# BootSel-Atmega.net
KiCad netlist of a schematic drawn in EAGLE
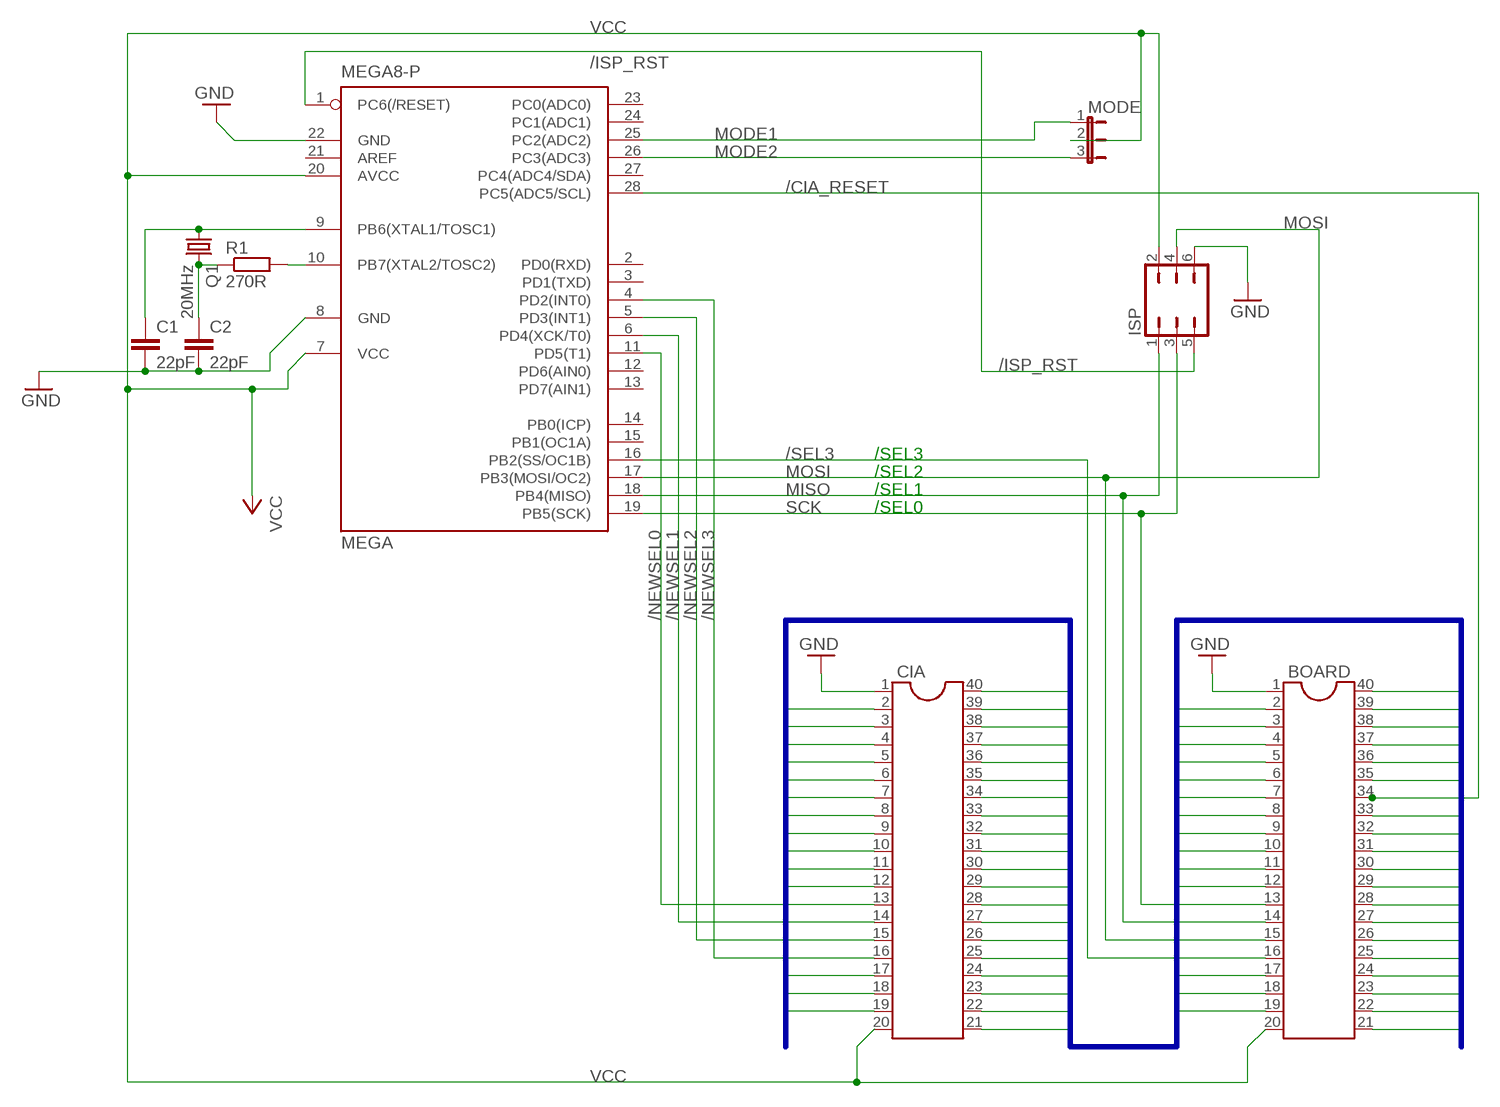
[diagram p0: schematic, sheet 1]

(export (version "E")
  (design (tool "Eeschema 10.0.6"))
  (components
    (comp (ref "BOARD")
      (value "DIL40")
      (footprint "eagle-import:DIL40")
      (libsource (lib "eagle-import") (part "DIL40"))
    )
    (comp (ref "C1")
      (value "22pF")
      (footprint "eagle-import:C2.5-4")
      (libsource (lib "eagle-import") (part "C2.5/4"))
    )
    (comp (ref "C2")
      (value "22pF")
      (footprint "eagle-import:C2.5-4")
      (libsource (lib "eagle-import") (part "C2.5/4"))
    )
    (comp (ref "CIA")
      (value "DIL40")
      (footprint "eagle-import:DIL40")
      (libsource (lib "eagle-import") (part "DIL40"))
    )
    (comp (ref "ISP")
      (value "JP3Q")
      (footprint "eagle-import:JP3Q")
      (libsource (lib "eagle-import") (part "JP3Q"))
    )
    (comp (ref "MEGA")
      (value "MEGA8-P")
      (footprint "eagle-import:DIL28-3")
      (libsource (lib "eagle-import") (part "MEGA8-P"))
    )
    (comp (ref "MODE")
      (value "JP2E")
      (footprint "eagle-import:JP2")
      (libsource (lib "eagle-import") (part "JP2E"))
    )
    (comp (ref "Q1")
      (value "20MHz")
      (footprint "eagle-import:HC49_S")
      (libsource (lib "eagle-import") (part "CRYSTALHC49S"))
    )
    (comp (ref "R1")
      (value "270R")
      (footprint "eagle-import:0204_5")
      (libsource (lib "eagle-import") (part "R-EU_0204/5"))
    )
  )
  (nets
    (net (code "1") (name "/CIA2") (class "Default")
      (node (ref "BOARD") (pin "2") (pinfunction "2_2") (pintype "passive"))
      (node (ref "CIA") (pin "2") (pinfunction "2_2") (pintype "passive"))
    )
    (net (code "2") (name "/CIA3") (class "Default")
      (node (ref "BOARD") (pin "3") (pinfunction "3_3") (pintype "passive"))
      (node (ref "CIA") (pin "3") (pinfunction "3_3") (pintype "passive"))
    )
    (net (code "3") (name "/CIA4") (class "Default")
      (node (ref "BOARD") (pin "4") (pinfunction "4_4") (pintype "passive"))
      (node (ref "CIA") (pin "4") (pinfunction "4_4") (pintype "passive"))
    )
    (net (code "4") (name "/CIA5") (class "Default")
      (node (ref "BOARD") (pin "5") (pinfunction "5_5") (pintype "passive"))
      (node (ref "CIA") (pin "5") (pinfunction "5_5") (pintype "passive"))
    )
    (net (code "5") (name "/CIA6") (class "Default")
      (node (ref "BOARD") (pin "6") (pinfunction "6_6") (pintype "passive"))
      (node (ref "CIA") (pin "6") (pinfunction "6_6") (pintype "passive"))
    )
    (net (code "6") (name "/CIA7") (class "Default")
      (node (ref "BOARD") (pin "7") (pinfunction "7_7") (pintype "passive"))
      (node (ref "CIA") (pin "7") (pinfunction "7_7") (pintype "passive"))
    )
    (net (code "7") (name "/CIA8") (class "Default")
      (node (ref "BOARD") (pin "8") (pinfunction "8_8") (pintype "passive"))
      (node (ref "CIA") (pin "8") (pinfunction "8_8") (pintype "passive"))
    )
    (net (code "8") (name "/CIA9") (class "Default")
      (node (ref "BOARD") (pin "9") (pinfunction "9_9") (pintype "passive"))
      (node (ref "CIA") (pin "9") (pinfunction "9_9") (pintype "passive"))
    )
    (net (code "9") (name "/CIA10") (class "Default")
      (node (ref "BOARD") (pin "10") (pinfunction "10_10") (pintype "passive"))
      (node (ref "CIA") (pin "10") (pinfunction "10_10") (pintype "passive"))
    )
    (net (code "10") (name "/CIA11") (class "Default")
      (node (ref "BOARD") (pin "11") (pinfunction "11_11") (pintype "passive"))
      (node (ref "CIA") (pin "11") (pinfunction "11_11") (pintype "passive"))
    )
    (net (code "11") (name "/CIA12") (class "Default")
      (node (ref "BOARD") (pin "12") (pinfunction "12_12") (pintype "passive"))
      (node (ref "CIA") (pin "12") (pinfunction "12_12") (pintype "passive"))
    )
    (net (code "12") (name "/CIA17") (class "Default")
      (node (ref "BOARD") (pin "17") (pinfunction "17_17") (pintype "passive"))
      (node (ref "CIA") (pin "17") (pinfunction "17_17") (pintype "passive"))
    )
    (net (code "13") (name "/CIA18") (class "Default")
      (node (ref "BOARD") (pin "18") (pinfunction "18_18") (pintype "passive"))
      (node (ref "CIA") (pin "18") (pinfunction "18_18") (pintype "passive"))
    )
    (net (code "14") (name "/CIA19") (class "Default")
      (node (ref "BOARD") (pin "19") (pinfunction "19_19") (pintype "passive"))
      (node (ref "CIA") (pin "19") (pinfunction "19_19") (pintype "passive"))
    )
    (net (code "15") (name "/CIA21") (class "Default")
      (node (ref "BOARD") (pin "21") (pinfunction "21_21") (pintype "passive"))
      (node (ref "CIA") (pin "21") (pinfunction "21_21") (pintype "passive"))
    )
    (net (code "16") (name "/CIA22") (class "Default")
      (node (ref "BOARD") (pin "22") (pinfunction "22_22") (pintype "passive"))
      (node (ref "CIA") (pin "22") (pinfunction "22_22") (pintype "passive"))
    )
    (net (code "17") (name "/CIA23") (class "Default")
      (node (ref "BOARD") (pin "23") (pinfunction "23_23") (pintype "passive"))
      (node (ref "CIA") (pin "23") (pinfunction "23_23") (pintype "passive"))
    )
    (net (code "18") (name "/CIA24") (class "Default")
      (node (ref "BOARD") (pin "24") (pinfunction "24_24") (pintype "passive"))
      (node (ref "CIA") (pin "24") (pinfunction "24_24") (pintype "passive"))
    )
    (net (code "19") (name "/CIA25") (class "Default")
      (node (ref "BOARD") (pin "25") (pinfunction "25_25") (pintype "passive"))
      (node (ref "CIA") (pin "25") (pinfunction "25_25") (pintype "passive"))
    )
    (net (code "20") (name "/CIA26") (class "Default")
      (node (ref "BOARD") (pin "26") (pinfunction "26_26") (pintype "passive"))
      (node (ref "CIA") (pin "26") (pinfunction "26_26") (pintype "passive"))
    )
    (net (code "21") (name "/CIA27") (class "Default")
      (node (ref "BOARD") (pin "27") (pinfunction "27_27") (pintype "passive"))
      (node (ref "CIA") (pin "27") (pinfunction "27_27") (pintype "passive"))
    )
    (net (code "22") (name "/CIA28") (class "Default")
      (node (ref "BOARD") (pin "28") (pinfunction "28_28") (pintype "passive"))
      (node (ref "CIA") (pin "28") (pinfunction "28_28") (pintype "passive"))
    )
    (net (code "23") (name "/CIA29") (class "Default")
      (node (ref "BOARD") (pin "29") (pinfunction "29_29") (pintype "passive"))
      (node (ref "CIA") (pin "29") (pinfunction "29_29") (pintype "passive"))
    )
    (net (code "24") (name "/CIA30") (class "Default")
      (node (ref "BOARD") (pin "30") (pinfunction "30_30") (pintype "passive"))
      (node (ref "CIA") (pin "30") (pinfunction "30_30") (pintype "passive"))
    )
    (net (code "25") (name "/CIA31") (class "Default")
      (node (ref "BOARD") (pin "31") (pinfunction "31_31") (pintype "passive"))
      (node (ref "CIA") (pin "31") (pinfunction "31_31") (pintype "passive"))
    )
    (net (code "26") (name "/CIA32") (class "Default")
      (node (ref "BOARD") (pin "32") (pinfunction "32_32") (pintype "passive"))
      (node (ref "CIA") (pin "32") (pinfunction "32_32") (pintype "passive"))
    )
    (net (code "27") (name "/CIA33") (class "Default")
      (node (ref "BOARD") (pin "33") (pinfunction "33_33") (pintype "passive"))
      (node (ref "CIA") (pin "33") (pinfunction "33_33") (pintype "passive"))
    )
    (net (code "28") (name "/CIA35") (class "Default")
      (node (ref "BOARD") (pin "35") (pinfunction "35_35") (pintype "passive"))
      (node (ref "CIA") (pin "35") (pinfunction "35_35") (pintype "passive"))
    )
    (net (code "29") (name "/CIA36") (class "Default")
      (node (ref "BOARD") (pin "36") (pinfunction "36_36") (pintype "passive"))
      (node (ref "CIA") (pin "36") (pinfunction "36_36") (pintype "passive"))
    )
    (net (code "30") (name "/CIA37") (class "Default")
      (node (ref "BOARD") (pin "37") (pinfunction "37_37") (pintype "passive"))
      (node (ref "CIA") (pin "37") (pinfunction "37_37") (pintype "passive"))
    )
    (net (code "31") (name "/CIA38") (class "Default")
      (node (ref "BOARD") (pin "38") (pinfunction "38_38") (pintype "passive"))
      (node (ref "CIA") (pin "38") (pinfunction "38_38") (pintype "passive"))
    )
    (net (code "32") (name "/CIA39") (class "Default")
      (node (ref "BOARD") (pin "39") (pinfunction "39_39") (pintype "passive"))
      (node (ref "CIA") (pin "39") (pinfunction "39_39") (pintype "passive"))
    )
    (net (code "33") (name "/CIA40") (class "Default")
      (node (ref "BOARD") (pin "40") (pinfunction "40_40") (pintype "passive"))
      (node (ref "CIA") (pin "40") (pinfunction "40_40") (pintype "passive"))
    )
    (net (code "34") (name "/MISO") (class "Default")
      (node (ref "BOARD") (pin "14") (pinfunction "14_14") (pintype "passive"))
      (node (ref "ISP") (pin "1") (pinfunction "1_1") (pintype "passive"))
      (node (ref "MEGA") (pin "18") (pinfunction "PB4(MISO)_18") (pintype "bidirectional"))
    )
    (net (code "35") (name "/MODE1") (class "Default")
      (node (ref "MEGA") (pin "25") (pinfunction "PC2(ADC2)_25") (pintype "bidirectional"))
      (node (ref "MODE") (pin "1") (pinfunction "1_1") (pintype "passive"))
    )
    (net (code "36") (name "/MODE2") (class "Default")
      (node (ref "MEGA") (pin "26") (pinfunction "PC3(ADC3)_26") (pintype "bidirectional"))
      (node (ref "MODE") (pin "3") (pinfunction "3_3") (pintype "passive"))
    )
    (net (code "37") (name "/MOSI") (class "Default")
      (node (ref "BOARD") (pin "15") (pinfunction "15_15") (pintype "passive"))
      (node (ref "ISP") (pin "4") (pinfunction "4_4") (pintype "passive"))
      (node (ref "MEGA") (pin "17") (pinfunction "PB3(MOSI/OC2)_17") (pintype "bidirectional"))
    )
    (net (code "38") (name "/SCK") (class "Default")
      (node (ref "BOARD") (pin "13") (pinfunction "13_13") (pintype "passive"))
      (node (ref "ISP") (pin "3") (pinfunction "3_3") (pintype "passive"))
      (node (ref "MEGA") (pin "19") (pinfunction "PB5(SCK)_19") (pintype "bidirectional"))
    )
    (net (code "39") (name "/{slash}CIA_RESET") (class "Default")
      (node (ref "BOARD") (pin "34") (pinfunction "34_34") (pintype "passive"))
      (node (ref "CIA") (pin "34") (pinfunction "34_34") (pintype "passive"))
      (node (ref "MEGA") (pin "28") (pinfunction "PC5(ADC5/SCL)_28") (pintype "bidirectional"))
    )
    (net (code "40") (name "/{slash}ISP_RST") (class "Default")
      (node (ref "ISP") (pin "5") (pinfunction "5_5") (pintype "passive"))
      (node (ref "MEGA") (pin "1") (pinfunction "PC6(/RESET)_1") (pintype "bidirectional"))
    )
    (net (code "41") (name "/{slash}NEWSEL0") (class "Default")
      (node (ref "CIA") (pin "13") (pinfunction "13_13") (pintype "passive"))
      (node (ref "MEGA") (pin "11") (pinfunction "PD5(T1)_11") (pintype "bidirectional"))
    )
    (net (code "42") (name "/{slash}NEWSEL1") (class "Default")
      (node (ref "CIA") (pin "14") (pinfunction "14_14") (pintype "passive"))
      (node (ref "MEGA") (pin "6") (pinfunction "PD4(XCK/T0)_6") (pintype "bidirectional"))
    )
    (net (code "43") (name "/{slash}NEWSEL2") (class "Default")
      (node (ref "CIA") (pin "15") (pinfunction "15_15") (pintype "passive"))
      (node (ref "MEGA") (pin "5") (pinfunction "PD3(INT1)_5") (pintype "bidirectional"))
    )
    (net (code "44") (name "/{slash}NEWSEL3") (class "Default")
      (node (ref "CIA") (pin "16") (pinfunction "16_16") (pintype "passive"))
      (node (ref "MEGA") (pin "4") (pinfunction "PD2(INT0)_4") (pintype "bidirectional"))
    )
    (net (code "45") (name "/{slash}SEL3") (class "Default")
      (node (ref "BOARD") (pin "16") (pinfunction "16_16") (pintype "passive"))
      (node (ref "MEGA") (pin "16") (pinfunction "PB2(SS/OC1B)_16") (pintype "bidirectional"))
    )
    (net (code "46") (name "GND") (class "Default")
      (node (ref "BOARD") (pin "1") (pinfunction "1_1") (pintype "passive"))
      (node (ref "C1") (pin "2") (pinfunction "2_2") (pintype "passive"))
      (node (ref "C2") (pin "2") (pinfunction "2_2") (pintype "passive"))
      (node (ref "CIA") (pin "1") (pinfunction "1_1") (pintype "passive"))
      (node (ref "ISP") (pin "6") (pinfunction "6_6") (pintype "passive"))
      (node (ref "MEGA") (pin "22") (pinfunction "GND_22") (pintype "power_in"))
      (node (ref "MEGA") (pin "8") (pinfunction "GND_8") (pintype "power_in"))
    )
    (net (code "47") (name "Net-(C2-Pad1)") (class "Default")
      (node (ref "C2") (pin "1") (pinfunction "1_1") (pintype "passive"))
      (node (ref "Q1") (pin "2") (pinfunction "2_2") (pintype "passive"))
      (node (ref "R1") (pin "1") (pinfunction "1_1") (pintype "passive"))
    )
    (net (code "48") (name "Net-(MEGA-PB6(XTAL1{slash}TOSC1))") (class "Default")
      (node (ref "C1") (pin "1") (pinfunction "1_1") (pintype "passive"))
      (node (ref "MEGA") (pin "9") (pinfunction "PB6(XTAL1/TOSC1)_9") (pintype "bidirectional"))
      (node (ref "Q1") (pin "1") (pinfunction "1_1") (pintype "passive"))
    )
    (net (code "49") (name "Net-(MEGA-PB7(XTAL2{slash}TOSC2))") (class "Default")
      (node (ref "MEGA") (pin "10") (pinfunction "PB7(XTAL2/TOSC2)_10") (pintype "bidirectional"))
      (node (ref "R1") (pin "2") (pinfunction "2_2") (pintype "passive"))
    )
    (net (code "50") (name "VCC") (class "Default")
      (node (ref "BOARD") (pin "20") (pinfunction "20_20") (pintype "passive"))
      (node (ref "CIA") (pin "20") (pinfunction "20_20") (pintype "passive"))
      (node (ref "ISP") (pin "2") (pinfunction "2_2") (pintype "passive"))
      (node (ref "MEGA") (pin "20") (pinfunction "AVCC_20") (pintype "power_in"))
      (node (ref "MEGA") (pin "7") (pinfunction "VCC_7") (pintype "power_in"))
      (node (ref "MODE") (pin "2") (pinfunction "2_2") (pintype "passive"))
    )
    (net (code "51") (name "unconnected-(MEGA-AREF-Pad21)") (class "Default")
      (node (ref "MEGA") (pin "21") (pinfunction "AREF_21") (pintype "passive"))
    )
    (net (code "52") (name "unconnected-(MEGA-PB0(ICP)-Pad14)") (class "Default")
      (node (ref "MEGA") (pin "14") (pinfunction "PB0(ICP)_14") (pintype "bidirectional"))
    )
    (net (code "53") (name "unconnected-(MEGA-PB1(OC1A)-Pad15)") (class "Default")
      (node (ref "MEGA") (pin "15") (pinfunction "PB1(OC1A)_15") (pintype "bidirectional"))
    )
    (net (code "54") (name "unconnected-(MEGA-PC0(ADC0)-Pad23)") (class "Default")
      (node (ref "MEGA") (pin "23") (pinfunction "PC0(ADC0)_23") (pintype "bidirectional"))
    )
    (net (code "55") (name "unconnected-(MEGA-PC1(ADC1)-Pad24)") (class "Default")
      (node (ref "MEGA") (pin "24") (pinfunction "PC1(ADC1)_24") (pintype "bidirectional"))
    )
    (net (code "56") (name "unconnected-(MEGA-PC4(ADC4{slash}SDA)-Pad27)") (class "Default")
      (node (ref "MEGA") (pin "27") (pinfunction "PC4(ADC4/SDA)_27") (pintype "bidirectional"))
    )
    (net (code "57") (name "unconnected-(MEGA-PD0(RXD)-Pad2)") (class "Default")
      (node (ref "MEGA") (pin "2") (pinfunction "PD0(RXD)_2") (pintype "bidirectional"))
    )
    (net (code "58") (name "unconnected-(MEGA-PD1(TXD)-Pad3)") (class "Default")
      (node (ref "MEGA") (pin "3") (pinfunction "PD1(TXD)_3") (pintype "bidirectional"))
    )
    (net (code "59") (name "unconnected-(MEGA-PD6(AIN0)-Pad12)") (class "Default")
      (node (ref "MEGA") (pin "12") (pinfunction "PD6(AIN0)_12") (pintype "bidirectional"))
    )
    (net (code "60") (name "unconnected-(MEGA-PD7(AIN1)-Pad13)") (class "Default")
      (node (ref "MEGA") (pin "13") (pinfunction "PD7(AIN1)_13") (pintype "bidirectional"))
    )
  )
)
